# RPi-CM-Adapter.net
KiCad netlist of a schematic drawn in Altium Designer
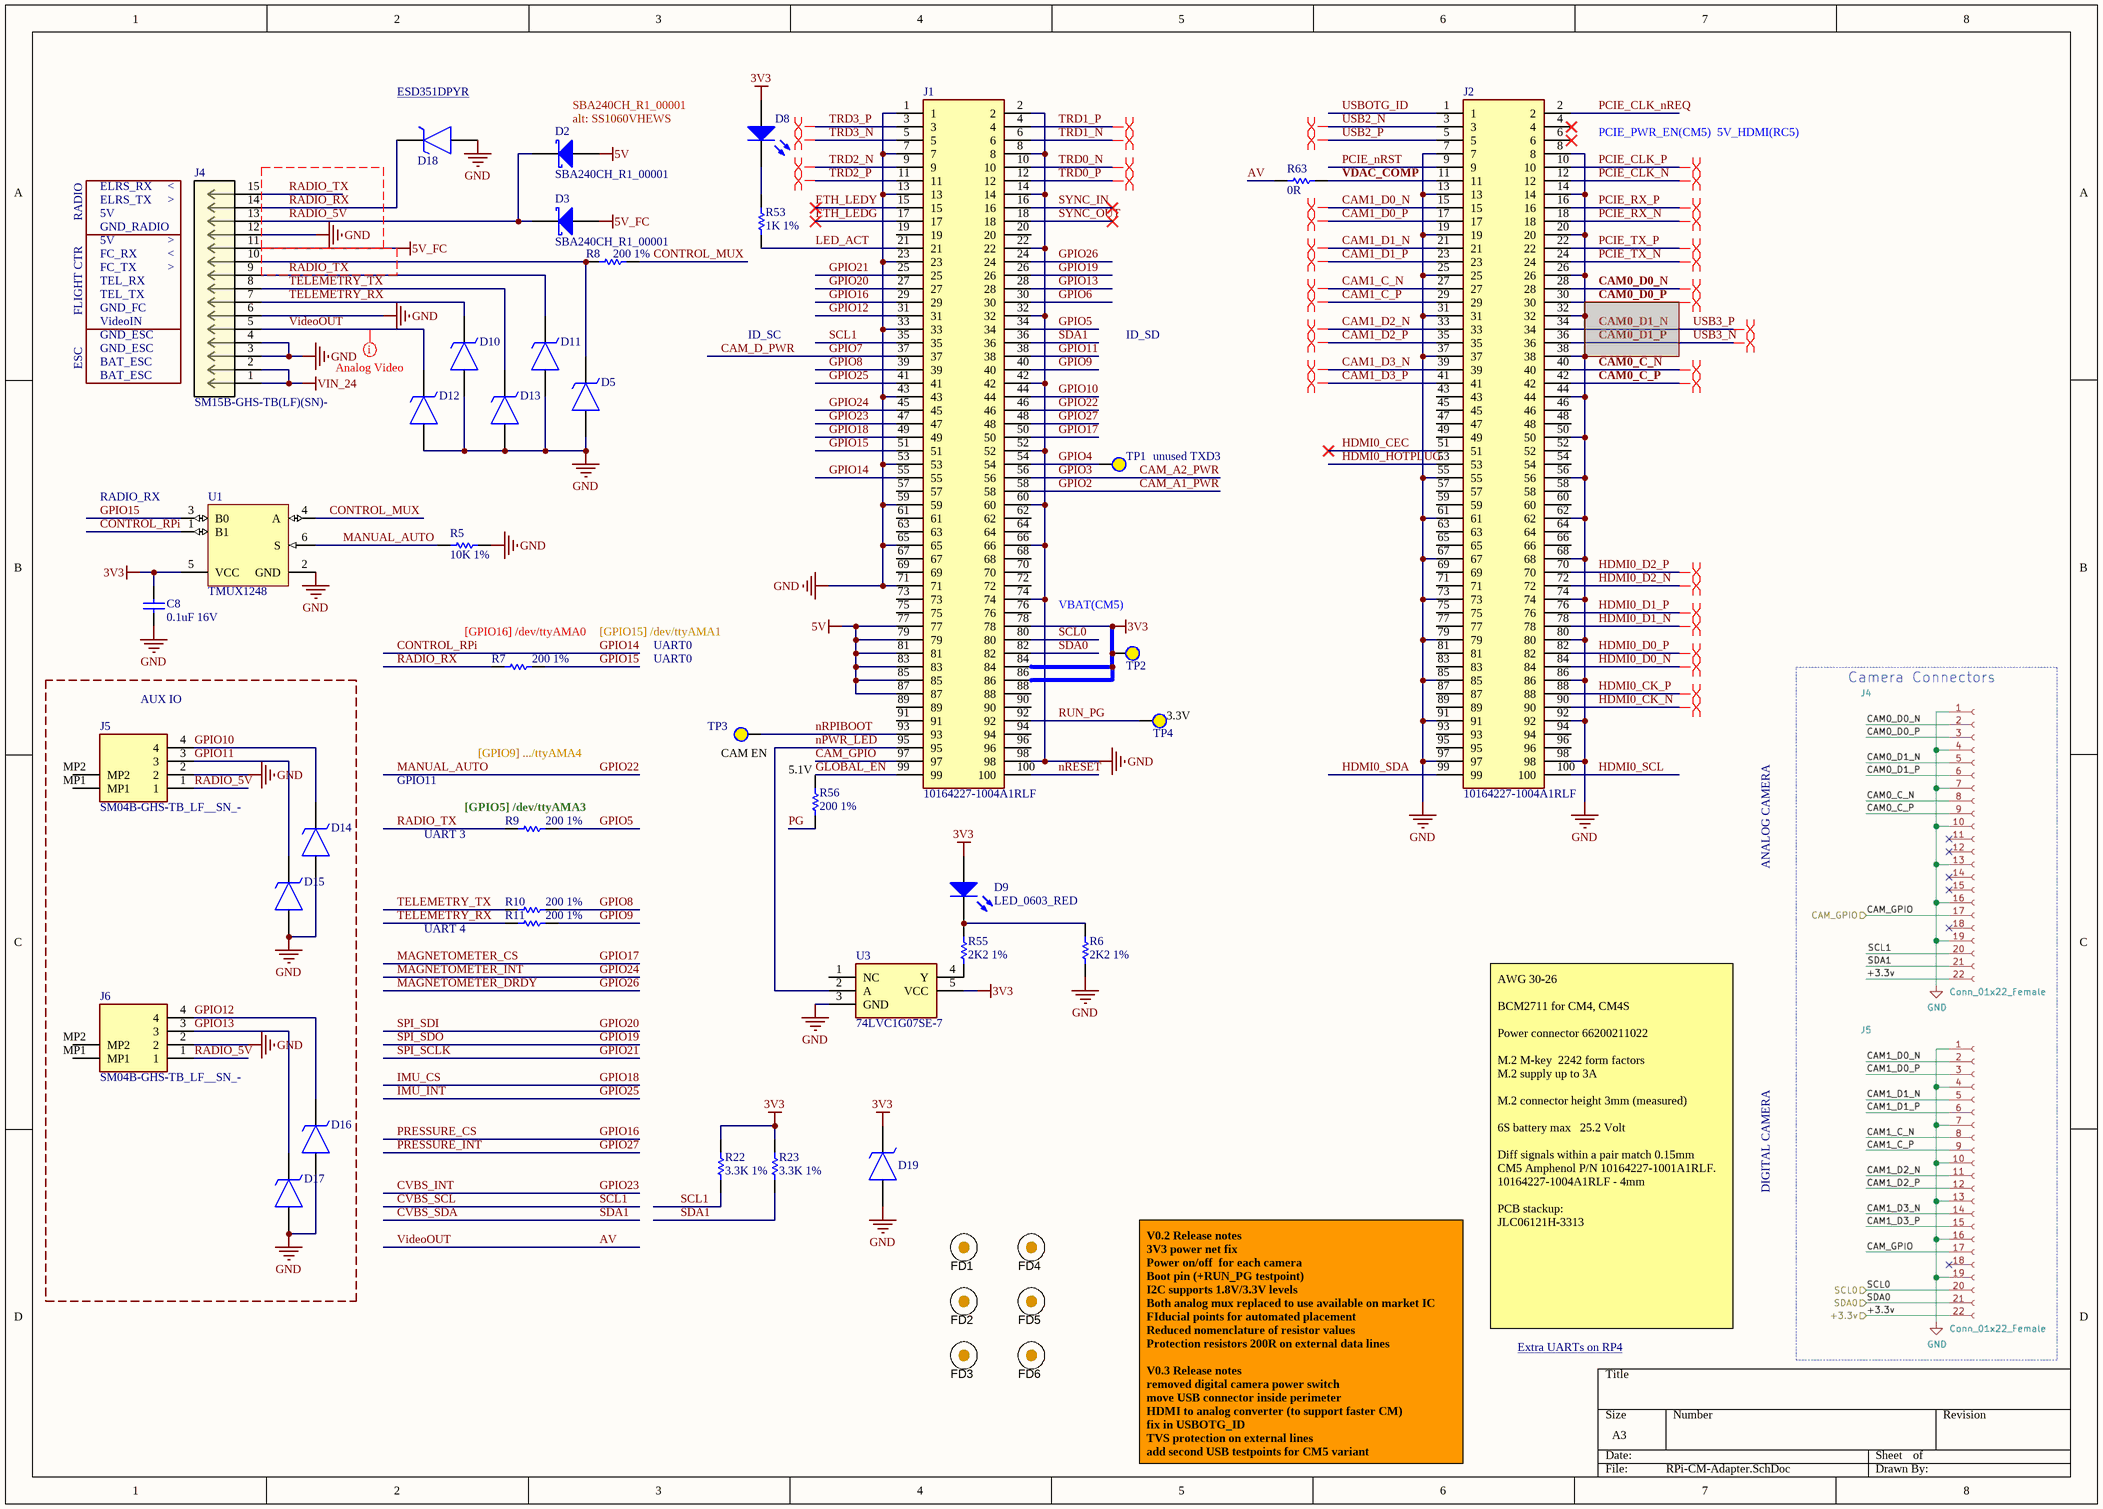
[diagram p0: RPi-CM-Adapter.SchDoc]

(export (version "E")
  (design (tool "Eeschema 10.0.6"))
  (components
    (comp (ref "C8")
      (value "0.1uF 16V")
      (footprint "0402")
      (description "0402 0.1 uF 16V ±10% Tolerance X7R SMT Multilayer Ceramic Capacitor")
      (fields
        (field (name "MANUFACTURER") "Murata")
        (field (name "MANUFACTURER PART NUMBER") "GCM155R71C104KA55J")
      )
      (libsource (lib "MyCustomLibrary") (part "Cap0.1UF_16V_X7R"))
    )
    (comp (ref "D2")
      (value "SBA240CH_R1_00001")
      (footprint "SOD-323HE")
      (description "Diode Schottky 40V 2A SOD323HE")
      (fields (field (name "MANUFACTURER") "Pan Jit"))
      (libsource (lib "MyCustomLibrary") (part "Diode SBA240CH_R1_00001"))
    )
    (comp (ref "D3")
      (value "SBA240CH_R1_00001")
      (footprint "SOD-323HE")
      (description "Diode Schottky 40V 2A SOD323HE")
      (fields (field (name "MANUFACTURER") "Pan Jit"))
      (libsource (lib "MyCustomLibrary") (part "Diode SBA240CH_R1_00001"))
    )
    (comp (ref "D5")
      (value "ESD351DPYR")
      (footprint "UCLAMP2501TTCT")
      (fields (field (name "MANUFACTURER") "Texas Instruments"))
      (libsource (lib "MyCustomLibrary") (part "ESD351DPYR"))
    )
    (comp (ref "D8")
      (value "LED_0603_GREEN")
      (footprint "1608[0603]_DIODE")
      (description "Typical GREEN LED")
      (fields
        (field (name "MANUFACTURER") "Rohm Semiconductor")
        (field (name "MANUFACTURER PART NUMBER") "SML-310MTT86")
      )
      (libsource (lib "MyCustomLibrary") (part "LED_0603_GREEN"))
    )
    (comp (ref "D9")
      (value "LED_0603_RED")
      (footprint "1608[0603]_DIODE")
      (description "Typical RED LED")
      (fields
        (field (name "MANUFACTURER") "Lite-On Inc.")
        (field (name "MANUFACTURER PART NUMBER") "LTST-C193KRKT-5A")
      )
      (libsource (lib "MyCustomLibrary") (part "LED_0603_RED"))
    )
    (comp (ref "D10")
      (value "ESD351DPYR")
      (footprint "UCLAMP2501TTCT")
      (fields (field (name "MANUFACTURER") "Texas Instruments"))
      (libsource (lib "MyCustomLibrary") (part "ESD351DPYR"))
    )
    (comp (ref "D11")
      (value "ESD351DPYR")
      (footprint "UCLAMP2501TTCT")
      (fields (field (name "MANUFACTURER") "Texas Instruments"))
      (libsource (lib "MyCustomLibrary") (part "ESD351DPYR"))
    )
    (comp (ref "D12")
      (value "ESD351DPYR")
      (footprint "UCLAMP2501TTCT")
      (fields (field (name "MANUFACTURER") "Texas Instruments"))
      (libsource (lib "MyCustomLibrary") (part "ESD351DPYR"))
    )
    (comp (ref "D13")
      (value "ESD351DPYR")
      (footprint "UCLAMP2501TTCT")
      (fields (field (name "MANUFACTURER") "Texas Instruments"))
      (libsource (lib "MyCustomLibrary") (part "ESD351DPYR"))
    )
    (comp (ref "D14")
      (value "ESD351DPYR")
      (footprint "UCLAMP2501TTCT")
      (fields (field (name "MANUFACTURER") "Texas Instruments"))
      (libsource (lib "MyCustomLibrary") (part "ESD351DPYR"))
    )
    (comp (ref "D15")
      (value "ESD351DPYR")
      (footprint "UCLAMP2501TTCT")
      (fields (field (name "MANUFACTURER") "Texas Instruments"))
      (libsource (lib "MyCustomLibrary") (part "ESD351DPYR"))
    )
    (comp (ref "D16")
      (value "ESD351DPYR")
      (footprint "UCLAMP2501TTCT")
      (fields (field (name "MANUFACTURER") "Texas Instruments"))
      (libsource (lib "MyCustomLibrary") (part "ESD351DPYR"))
    )
    (comp (ref "D17")
      (value "ESD351DPYR")
      (footprint "UCLAMP2501TTCT")
      (fields (field (name "MANUFACTURER") "Texas Instruments"))
      (libsource (lib "MyCustomLibrary") (part "ESD351DPYR"))
    )
    (comp (ref "D18")
      (value "ESD351DPYR")
      (footprint "UCLAMP2501TTCT")
      (fields (field (name "MANUFACTURER") "Texas Instruments"))
      (libsource (lib "MyCustomLibrary") (part "ESD351DPYR"))
    )
    (comp (ref "D19")
      (value "ESD351DPYR")
      (footprint "UCLAMP2501TTCT")
      (fields (field (name "MANUFACTURER") "Texas Instruments"))
      (libsource (lib "MyCustomLibrary") (part "ESD351DPYR"))
    )
    (comp (ref "FD1")
      (value "Fiducial")
      (footprint "Fiducial10-20")
      (description "Fiducial mark.  There is nothing to buy or mount.")
      (fields (field (name "SYMBOLCREATOR") "codlsc") (field (name "PUBLISHER") "National Semiconductor"))
      (libsource (lib "MyCustomLibrary") (part "Fiducial"))
    )
    (comp (ref "FD2")
      (value "Fiducial")
      (footprint "Fiducial10-20")
      (description "Fiducial mark.  There is nothing to buy or mount.")
      (fields (field (name "SYMBOLCREATOR") "codlsc") (field (name "PUBLISHER") "National Semiconductor"))
      (libsource (lib "MyCustomLibrary") (part "Fiducial"))
    )
    (comp (ref "FD3")
      (value "Fiducial")
      (footprint "Fiducial10-20")
      (description "Fiducial mark.  There is nothing to buy or mount.")
      (fields (field (name "SYMBOLCREATOR") "codlsc") (field (name "PUBLISHER") "National Semiconductor"))
      (libsource (lib "MyCustomLibrary") (part "Fiducial"))
    )
    (comp (ref "FD4")
      (value "Fiducial")
      (footprint "Fiducial10-20")
      (description "Fiducial mark.  There is nothing to buy or mount.")
      (fields (field (name "SYMBOLCREATOR") "codlsc") (field (name "PUBLISHER") "National Semiconductor"))
      (libsource (lib "MyCustomLibrary") (part "Fiducial"))
    )
    (comp (ref "FD5")
      (value "Fiducial")
      (footprint "Fiducial10-20")
      (description "Fiducial mark.  There is nothing to buy or mount.")
      (fields (field (name "SYMBOLCREATOR") "codlsc") (field (name "PUBLISHER") "National Semiconductor"))
      (libsource (lib "MyCustomLibrary") (part "Fiducial"))
    )
    (comp (ref "FD6")
      (value "Fiducial")
      (footprint "Fiducial10-20")
      (description "Fiducial mark.  There is nothing to buy or mount.")
      (fields (field (name "SYMBOLCREATOR") "codlsc") (field (name "PUBLISHER") "National Semiconductor"))
      (libsource (lib "MyCustomLibrary") (part "Fiducial"))
    )
    (comp (ref "J1")
      (value "10164227-1004A1RLF")
      (footprint "MyConnectors:101642271004A1RLF")
      (description "Connector")
      (fields (field (name "MOUSER PART NUMBER") "649-101642271004RLF"))
      (libsource (lib "MyConnectors") (part "10164227-1004A1RLF"))
    )
    (comp (ref "J2")
      (value "10164227-1004A1RLF")
      (footprint "MyConnectors:101642271004A1RLF")
      (description "Connector")
      (fields (field (name "MOUSER PART NUMBER") "649-101642271004RLF"))
      (libsource (lib "MyConnectors") (part "10164227-1004A1RLF"))
    )
    (comp (ref "J4")
      (value "SM15B-GHS-TB(LF)(SN)-")
      (footprint "MyConnectors:CONN_SM15B-GHS-TB")
      (description "No Description Available")
      (libsource (lib "MyConnectors") (part "SM15B-GHS-TB(LF)(SN)-"))
    )
    (comp (ref "J5")
      (value "SM04B-GHS-TB_LF__SN_-")
      (footprint "MyConnectors:SM04BGHSTBLFSN")
      (description "Conn Shrouded Header (4 Sides) HDR 4 POS 1.25mm Solder RA Side Entry SMD T/R")
      (fields
        (field (name "MANUFACTURER_PART_NUMBER") "SM04B-GHS-TB(LF)(SN)-")
        (field (name "MANUFACTURER") "JST")
      )
      (libsource (lib "MyConnectors") (part "SM04B-GHS-TB_LF__SN_-"))
    )
    (comp (ref "J6")
      (value "SM04B-GHS-TB_LF__SN_-")
      (footprint "MyConnectors:SM04BGHSTBLFSN")
      (description "Conn Shrouded Header (4 Sides) HDR 4 POS 1.25mm Solder RA Side Entry SMD T/R")
      (fields
        (field (name "MANUFACTURER_PART_NUMBER") "SM04B-GHS-TB(LF)(SN)-")
        (field (name "MANUFACTURER") "JST")
      )
      (libsource (lib "MyConnectors") (part "SM04B-GHS-TB_LF__SN_-"))
    )
    (comp (ref "R5")
      (value "10K 1%")
      (footprint "0402")
      (description "Resistor")
      (fields
        (field (name "MANUFACTURER") "Yageo")
        (field (name "MANUFACTURER PART NUMBER") "RC0402FR-0710KL")
      )
      (libsource (lib "MyCustomLibrary") (part "Res_10K_0402"))
    )
    (comp (ref "R6")
      (value "2K2 1%")
      (footprint "0402")
      (description "SMD Chip Resistor, 2.2 kOhm, ± 1%, 63 mW, 0402 [1005 Metric], Thick Film, Anti-Sulfur")
      (fields
        (field (name "MANUFACTURER") "Yageo")
        (field (name "MANUFACTURER PART NUMBER") "AF0402FR-072K2L")
      )
      (libsource (lib "MyCustomLibrary") (part "Res_2K2_0402"))
    )
    (comp (ref "R7")
      (value "200 1%")
      (footprint "0402")
      (description "Resistor")
      (libsource (lib "MyCustomLibrary") (part "Res_200R_0402"))
    )
    (comp (ref "R8")
      (value "200 1%")
      (footprint "0402")
      (description "Resistor")
      (libsource (lib "MyCustomLibrary") (part "Res_200R_0402"))
    )
    (comp (ref "R9")
      (value "200 1%")
      (footprint "0402")
      (description "Resistor")
      (libsource (lib "MyCustomLibrary") (part "Res_200R_0402"))
    )
    (comp (ref "R10")
      (value "200 1%")
      (footprint "0402")
      (description "Resistor")
      (libsource (lib "MyCustomLibrary") (part "Res_200R_0402"))
    )
    (comp (ref "R11")
      (value "200 1%")
      (footprint "0402")
      (description "Resistor")
      (libsource (lib "MyCustomLibrary") (part "Res_200R_0402"))
    )
    (comp (ref "R22")
      (value "3.3K 1%")
      (footprint "0402")
      (description "SMD Chip Resistor, Thick Film, 3.3 kohm, 50 V, 0402 [1005 Metric], 1%")
      (fields
        (field (name "MANUFACTURER") "Yageo")
        (field (name "MANUFACTURER PART NUMBER") "RC0402FR-073K3L")
      )
      (libsource (lib "MyCustomLibrary") (part "Res_3K3_0402"))
    )
    (comp (ref "R23")
      (value "3.3K 1%")
      (footprint "0402")
      (description "SMD Chip Resistor, Thick Film, 3.3 kohm, 50 V, 0402 [1005 Metric], 1%")
      (fields
        (field (name "MANUFACTURER") "Yageo")
        (field (name "MANUFACTURER PART NUMBER") "RC0402FR-073K3L")
      )
      (libsource (lib "MyCustomLibrary") (part "Res_3K3_0402"))
    )
    (comp (ref "R53")
      (value "1K 1%")
      (footprint "0402")
      (description "Resistor 1K 1% 0402")
      (fields
        (field (name "MANUFACTURER") "Yageo")
        (field (name "MANUFACTURER PART NUMBER") "RC0402FR-071KL")
      )
      (libsource (lib "MyCustomLibrary") (part "Res_1K_0402"))
    )
    (comp (ref "R55")
      (value "2K2 1%")
      (footprint "0402")
      (description "SMD Chip Resistor, 2.2 kOhm, ± 1%, 63 mW, 0402 [1005 Metric], Thick Film, Anti-Sulfur")
      (fields
        (field (name "MANUFACTURER") "Yageo")
        (field (name "MANUFACTURER PART NUMBER") "AF0402FR-072K2L")
      )
      (libsource (lib "MyCustomLibrary") (part "Res_2K2_0402"))
    )
    (comp (ref "R56")
      (value "200 1%")
      (footprint "0402")
      (description "Resistor")
      (libsource (lib "MyCustomLibrary") (part "Res_200R_0402"))
    )
    (comp (ref "R63")
      (value "0R")
      (footprint "0402")
      (description "Zero ohm Jumper 0402")
      (fields (field (name "TOLERANCE") "Jumper") (field (name "MANUFACTURER") "Yageo"))
      (libsource (lib "MyCustomLibrary") (part "Res_0R_0402"))
    )
    (comp (ref "TP1")
      (value "TESTPOINT")
      (footprint "TESTPOINT_0.9")
      (libsource (lib "MyCustomLibrary") (part "TESTPOINT"))
    )
    (comp (ref "TP2")
      (value "TESTPOINT")
      (footprint "TESTPOINT_0.9")
      (libsource (lib "MyCustomLibrary") (part "TESTPOINT"))
    )
    (comp (ref "TP3")
      (value "TESTPOINT")
      (footprint "TESTPOINT_0.9")
      (libsource (lib "MyCustomLibrary") (part "TESTPOINT"))
    )
    (comp (ref "TP4")
      (value "TESTPOINT")
      (footprint "TESTPOINT_0.9")
      (libsource (lib "MyCustomLibrary") (part "TESTPOINT"))
    )
    (comp (ref "U1")
      (value "TMUX1248")
      (footprint "FAIR-SC70-6_V")
      (description "3-Ω low RON, 5-V, 2: 1 (SPDT) general purpose switch with 3157 pinout 6-SC70 -40 to 125")
      (fields
        (field (name "MANUFACTURER") "Texas Instruments")
        (field (name "MANUFACTURER PART NUMBER") "TMUX1248DCKR")
      )
      (libsource (lib "MyCustomLibrary") (part "TMUX1248"))
    )
    (comp (ref "U3")
      (value "74LVC1G07SE-7")
      (footprint "SamacSys:SOT65P210X110-5N")
      (description "74LVC Series 5.5 V Surface Mount Single Buffer with Open Drain Output - SOT-353")
      (fields (field (name "MOUSER PART NUMBER") "621-74LVC1G07SE-7") (field (name "MANUFACTURER") "Diodes"))
      (libsource (lib "MyCustomLibrary") (part "74LVC1G07SE-7"))
    )
  )
  (nets
    (net (code "1") (name "/AV") (class "Default")
      (node (ref "D12") (pin "2") (pinfunction "K_2") (pintype "passive"))
      (node (ref "J4") (pin "5") (pinfunction "5_5") (pintype "passive"))
      (node (ref "R63") (pin "1") (pinfunction "1_1") (pintype "passive"))
    )
    (net (code "2") (name "/CAM0_C_N") (class "Default")
      (node (ref "J2") (pin "40") (pinfunction "40_40") (pintype "passive"))
    )
    (net (code "3") (name "/CAM0_C_P") (class "Default")
      (node (ref "J2") (pin "42") (pinfunction "42_42") (pintype "passive"))
    )
    (net (code "4") (name "/CAM0_D0_N") (class "Default")
      (node (ref "J2") (pin "28") (pinfunction "28_28") (pintype "passive"))
    )
    (net (code "5") (name "/CAM0_D0_P") (class "Default")
      (node (ref "J2") (pin "30") (pinfunction "30_30") (pintype "passive"))
    )
    (net (code "6") (name "/CAM0_D1_N") (class "Default")
      (node (ref "J2") (pin "34") (pinfunction "34_34") (pintype "passive"))
    )
    (net (code "7") (name "/CAM0_D1_P") (class "Default")
      (node (ref "J2") (pin "36") (pinfunction "36_36") (pintype "passive"))
    )
    (net (code "8") (name "/CAM1_C_N") (class "Default")
      (node (ref "J2") (pin "27") (pinfunction "27_27") (pintype "passive"))
    )
    (net (code "9") (name "/CAM1_C_P") (class "Default")
      (node (ref "J2") (pin "29") (pinfunction "29_29") (pintype "passive"))
    )
    (net (code "10") (name "/CAM1_D0_N") (class "Default")
      (node (ref "J2") (pin "15") (pinfunction "15_15") (pintype "passive"))
    )
    (net (code "11") (name "/CAM1_D0_P") (class "Default")
      (node (ref "J2") (pin "17") (pinfunction "17_17") (pintype "passive"))
    )
    (net (code "12") (name "/CAM1_D1_N") (class "Default")
      (node (ref "J2") (pin "21") (pinfunction "21_21") (pintype "passive"))
    )
    (net (code "13") (name "/CAM1_D1_P") (class "Default")
      (node (ref "J2") (pin "23") (pinfunction "23_23") (pintype "passive"))
    )
    (net (code "14") (name "/CAM1_D2_N") (class "Default")
      (node (ref "J2") (pin "33") (pinfunction "33_33") (pintype "passive"))
    )
    (net (code "15") (name "/CAM1_D2_P") (class "Default")
      (node (ref "J2") (pin "35") (pinfunction "35_35") (pintype "passive"))
    )
    (net (code "16") (name "/CAM1_D3_N") (class "Default")
      (node (ref "J2") (pin "39") (pinfunction "39_39") (pintype "passive"))
    )
    (net (code "17") (name "/CAM1_D3_P") (class "Default")
      (node (ref "J2") (pin "41") (pinfunction "41_41") (pintype "passive"))
    )
    (net (code "18") (name "/CAM_A1_PWR") (class "Default")
      (node (ref "J1") (pin "58") (pinfunction "58_58") (pintype "passive"))
    )
    (net (code "19") (name "/CAM_A2_PWR") (class "Default")
      (node (ref "J1") (pin "56") (pinfunction "56_56") (pintype "passive"))
    )
    (net (code "20") (name "/CAM_D_PWR") (class "Default")
      (node (ref "J1") (pin "37") (pinfunction "37_37") (pintype "passive"))
    )
    (net (code "21") (name "/CAM_GPIO") (class "Default")
      (node (ref "J1") (pin "97") (pinfunction "97_97") (pintype "passive"))
    )
    (net (code "22") (name "/CONTROL_MUX") (class "Default")
      (node (ref "R8") (pin "2") (pinfunction "2_2") (pintype "passive"))
      (node (ref "U1") (pin "4") (pinfunction "A_4") (pintype "bidirectional"))
    )
    (net (code "23") (name "/CONTROL_RPi") (class "Default")
      (node (ref "J1") (pin "55") (pinfunction "55_55") (pintype "passive"))
      (node (ref "U1") (pin "1") (pinfunction "B1_1") (pintype "bidirectional"))
    )
    (net (code "24") (name "/CVBS_INT") (class "Default")
      (node (ref "J1") (pin "47") (pinfunction "47_47") (pintype "passive"))
    )
    (net (code "25") (name "/CVBS_SCL") (class "Default")
      (node (ref "J1") (pin "35") (pinfunction "35_35") (pintype "passive"))
      (node (ref "R22") (pin "1") (pinfunction "1_1") (pintype "passive"))
    )
    (net (code "26") (name "/CVBS_SDA") (class "Default")
      (node (ref "J1") (pin "36") (pinfunction "36_36") (pintype "passive"))
      (node (ref "R23") (pin "1") (pinfunction "1_1") (pintype "passive"))
    )
    (net (code "27") (name "/ETH_LEDG") (class "Default")
      (node (ref "J1") (pin "17") (pinfunction "17_17") (pintype "passive+no_connect"))
    )
    (net (code "28") (name "/ETH_LEDY") (class "Default")
      (node (ref "J1") (pin "15") (pinfunction "15_15") (pintype "passive+no_connect"))
    )
    (net (code "29") (name "/GLOBAL_EN") (class "Default")
      (node (ref "J1") (pin "99") (pinfunction "99_99") (pintype "passive"))
      (node (ref "R56") (pin "2") (pinfunction "2_2") (pintype "passive"))
    )
    (net (code "30") (name "/GPIO4") (class "Default")
      (node (ref "J1") (pin "54") (pinfunction "54_54") (pintype "passive"))
      (node (ref "TP1") (pin "1") (pinfunction "1_1") (pintype "passive"))
    )
    (net (code "31") (name "/GPIO5") (class "Default")
      (node (ref "J1") (pin "34") (pinfunction "34_34") (pintype "passive"))
      (node (ref "R9") (pin "2") (pinfunction "2_2") (pintype "passive"))
    )
    (net (code "32") (name "/GPIO6") (class "Default")
      (node (ref "J1") (pin "30") (pinfunction "30_30") (pintype "passive"))
    )
    (net (code "33") (name "/GPIO8") (class "Default")
      (node (ref "J1") (pin "39") (pinfunction "39_39") (pintype "passive"))
      (node (ref "R10") (pin "2") (pinfunction "2_2") (pintype "passive"))
    )
    (net (code "34") (name "/GPIO9") (class "Default")
      (node (ref "J1") (pin "40") (pinfunction "40_40") (pintype "passive"))
      (node (ref "R11") (pin "2") (pinfunction "2_2") (pintype "passive"))
    )
    (net (code "35") (name "/GPIO10") (class "Default")
      (node (ref "D14") (pin "2") (pinfunction "K_2") (pintype "passive"))
      (node (ref "J1") (pin "44") (pinfunction "44_44") (pintype "passive"))
      (node (ref "J5") (pin "4") (pinfunction "4_4") (pintype "passive"))
    )
    (net (code "36") (name "/GPIO11") (class "Default")
      (node (ref "D15") (pin "2") (pinfunction "K_2") (pintype "passive"))
      (node (ref "J1") (pin "38") (pinfunction "38_38") (pintype "passive"))
      (node (ref "J5") (pin "3") (pinfunction "3_3") (pintype "passive"))
    )
    (net (code "37") (name "/GPIO12") (class "Default")
      (node (ref "D16") (pin "2") (pinfunction "K_2") (pintype "passive"))
      (node (ref "J1") (pin "31") (pinfunction "31_31") (pintype "passive"))
      (node (ref "J6") (pin "4") (pinfunction "4_4") (pintype "passive"))
    )
    (net (code "38") (name "/GPIO13") (class "Default")
      (node (ref "D17") (pin "2") (pinfunction "K_2") (pintype "passive"))
      (node (ref "J1") (pin "28") (pinfunction "28_28") (pintype "passive"))
      (node (ref "J6") (pin "3") (pinfunction "3_3") (pintype "passive"))
    )
    (net (code "39") (name "/GPIO15") (class "Default")
      (node (ref "J1") (pin "51") (pinfunction "51_51") (pintype "passive"))
      (node (ref "R7") (pin "1") (pinfunction "1_1") (pintype "passive"))
      (node (ref "U1") (pin "3") (pinfunction "B0_3") (pintype "bidirectional"))
    )
    (net (code "40") (name "/GPIO16") (class "Default")
      (node (ref "J1") (pin "29") (pinfunction "29_29") (pintype "passive"))
    )
    (net (code "41") (name "/GPIO17") (class "Default")
      (node (ref "J1") (pin "50") (pinfunction "50_50") (pintype "passive"))
    )
    (net (code "42") (name "/GPIO18") (class "Default")
      (node (ref "J1") (pin "49") (pinfunction "49_49") (pintype "passive"))
    )
    (net (code "43") (name "/GPIO19") (class "Default")
      (node (ref "J1") (pin "26") (pinfunction "26_26") (pintype "passive"))
    )
    (net (code "44") (name "/GPIO20") (class "Default")
      (node (ref "J1") (pin "27") (pinfunction "27_27") (pintype "passive"))
    )
    (net (code "45") (name "/GPIO21") (class "Default")
      (node (ref "J1") (pin "25") (pinfunction "25_25") (pintype "passive"))
    )
    (net (code "46") (name "/GPIO22") (class "Default")
      (node (ref "J1") (pin "46") (pinfunction "46_46") (pintype "passive"))
      (node (ref "R5") (pin "2") (pinfunction "2_2") (pintype "passive"))
      (node (ref "U1") (pin "6") (pinfunction "S_6") (pintype "input"))
    )
    (net (code "47") (name "/GPIO24") (class "Default")
      (node (ref "J1") (pin "45") (pinfunction "45_45") (pintype "passive"))
    )
    (net (code "48") (name "/GPIO25") (class "Default")
      (node (ref "J1") (pin "41") (pinfunction "41_41") (pintype "passive"))
    )
    (net (code "49") (name "/GPIO26") (class "Default")
      (node (ref "J1") (pin "24") (pinfunction "24_24") (pintype "passive"))
    )
    (net (code "50") (name "/GPIO27") (class "Default")
      (node (ref "J1") (pin "48") (pinfunction "48_48") (pintype "passive"))
    )
    (net (code "51") (name "/HDMI0_CEC") (class "Default")
      (node (ref "J2") (pin "51") (pinfunction "51_51") (pintype "passive+no_connect"))
    )
    (net (code "52") (name "/HDMI0_CK_N") (class "Default")
      (node (ref "J2") (pin "90") (pinfunction "90_90") (pintype "passive"))
    )
    (net (code "53") (name "/HDMI0_CK_P") (class "Default")
      (node (ref "J2") (pin "88") (pinfunction "88_88") (pintype "passive"))
    )
    (net (code "54") (name "/HDMI0_D0_N") (class "Default")
      (node (ref "J2") (pin "84") (pinfunction "84_84") (pintype "passive"))
    )
    (net (code "55") (name "/HDMI0_D0_P") (class "Default")
      (node (ref "J2") (pin "82") (pinfunction "82_82") (pintype "passive"))
    )
    (net (code "56") (name "/HDMI0_D1_N") (class "Default")
      (node (ref "J2") (pin "78") (pinfunction "78_78") (pintype "passive"))
    )
    (net (code "57") (name "/HDMI0_D1_P") (class "Default")
      (node (ref "J2") (pin "76") (pinfunction "76_76") (pintype "passive"))
    )
    (net (code "58") (name "/HDMI0_D2_N") (class "Default")
      (node (ref "J2") (pin "72") (pinfunction "72_72") (pintype "passive"))
    )
    (net (code "59") (name "/HDMI0_D2_P") (class "Default")
      (node (ref "J2") (pin "70") (pinfunction "70_70") (pintype "passive"))
    )
    (net (code "60") (name "/HDMI0_HOTPLUG") (class "Default")
      (node (ref "J2") (pin "53") (pinfunction "53_53") (pintype "passive"))
    )
    (net (code "61") (name "/HDMI0_SCL") (class "Default")
      (node (ref "J2") (pin "100") (pinfunction "100_100") (pintype "passive"))
    )
    (net (code "62") (name "/HDMI0_SDA") (class "Default")
      (node (ref "J2") (pin "99") (pinfunction "99_99") (pintype "passive"))
    )
    (net (code "63") (name "/LED_ACT") (class "Default")
      (node (ref "J1") (pin "21") (pinfunction "21_21") (pintype "passive"))
      (node (ref "R53") (pin "1") (pinfunction "1_1") (pintype "passive"))
    )
    (net (code "64") (name "/PCIE_CLK_N") (class "Default")
      (node (ref "J2") (pin "12") (pinfunction "12_12") (pintype "passive"))
    )
    (net (code "65") (name "/PCIE_CLK_P") (class "Default")
      (node (ref "J2") (pin "10") (pinfunction "10_10") (pintype "passive"))
    )
    (net (code "66") (name "/PCIE_CLK_nREQ") (class "Default")
      (node (ref "J2") (pin "2") (pinfunction "2_2") (pintype "passive"))
    )
    (net (code "67") (name "/PCIE_RX_N") (class "Default")
      (node (ref "J2") (pin "18") (pinfunction "18_18") (pintype "passive"))
    )
    (net (code "68") (name "/PCIE_RX_P") (class "Default")
      (node (ref "J2") (pin "16") (pinfunction "16_16") (pintype "passive"))
    )
    (net (code "69") (name "/PCIE_TX_N") (class "Default")
      (node (ref "J2") (pin "24") (pinfunction "24_24") (pintype "passive"))
    )
    (net (code "70") (name "/PCIE_TX_P") (class "Default")
      (node (ref "J2") (pin "22") (pinfunction "22_22") (pintype "passive"))
    )
    (net (code "71") (name "/PCIE_nRST") (class "Default")
      (node (ref "J2") (pin "9") (pinfunction "9_9") (pintype "passive"))
    )
    (net (code "72") (name "/PG") (class "Default")
      (node (ref "R56") (pin "1") (pinfunction "1_1") (pintype "passive"))
    )
    (net (code "73") (name "/RADIO_5V") (class "Default")
      (node (ref "D2") (pin "1") (pinfunction "K_1") (pintype "passive"))
      (node (ref "D3") (pin "1") (pinfunction "K_1") (pintype "passive"))
      (node (ref "J4") (pin "13") (pinfunction "13_13") (pintype "passive"))
      (node (ref "J5") (pin "1") (pinfunction "1_1") (pintype "passive"))
      (node (ref "J6") (pin "1") (pinfunction "1_1") (pintype "passive"))
    )
    (net (code "74") (name "/RADIO_RX") (class "Default")
      (node (ref "D18") (pin "2") (pinfunction "K_2") (pintype "passive"))
      (node (ref "J4") (pin "14") (pinfunction "14_14") (pintype "passive"))
      (node (ref "R7") (pin "2") (pinfunction "2_2") (pintype "passive"))
    )
    (net (code "75") (name "/RADIO_TX") (class "Default")
      (node (ref "D11") (pin "2") (pinfunction "K_2") (pintype "passive"))
      (node (ref "J4") (pin "15") (pinfunction "15_15") (pintype "passive"))
      (node (ref "J4") (pin "9") (pinfunction "9_9") (pintype "passive"))
      (node (ref "R9") (pin "1") (pinfunction "1_1") (pintype "passive"))
    )
    (net (code "76") (name "/RUN_PG") (class "Default")
      (node (ref "J1") (pin "92") (pinfunction "92_92") (pintype "passive"))
      (node (ref "TP4") (pin "1") (pinfunction "1_1") (pintype "passive"))
    )
    (net (code "77") (name "/SCL0") (class "Default")
      (node (ref "J1") (pin "80") (pinfunction "80_80") (pintype "passive"))
    )
    (net (code "78") (name "/SDA0") (class "Default")
      (node (ref "J1") (pin "82") (pinfunction "82_82") (pintype "passive"))
    )
    (net (code "79") (name "/SYNC_IN") (class "Default")
      (node (ref "J1") (pin "16") (pinfunction "16_16") (pintype "passive+no_connect"))
    )
    (net (code "80") (name "/SYNC_OUT") (class "Default")
      (node (ref "J1") (pin "18") (pinfunction "18_18") (pintype "passive+no_connect"))
    )
    (net (code "81") (name "/TELEMETRY_RX") (class "Default")
      (node (ref "D10") (pin "2") (pinfunction "K_2") (pintype "passive"))
      (node (ref "J4") (pin "7") (pinfunction "7_7") (pintype "passive"))
      (node (ref "R11") (pin "1") (pinfunction "1_1") (pintype "passive"))
    )
    (net (code "82") (name "/TELEMETRY_TX") (class "Default")
      (node (ref "D13") (pin "2") (pinfunction "K_2") (pintype "passive"))
      (node (ref "J4") (pin "8") (pinfunction "8_8") (pintype "passive"))
      (node (ref "R10") (pin "1") (pinfunction "1_1") (pintype "passive"))
    )
    (net (code "83") (name "/TRD0_N") (class "Default")
      (node (ref "J1") (pin "10") (pinfunction "10_10") (pintype "passive"))
    )
    (net (code "84") (name "/TRD0_P") (class "Default")
      (node (ref "J1") (pin "12") (pinfunction "12_12") (pintype "passive"))
    )
    (net (code "85") (name "/TRD1_N") (class "Default")
      (node (ref "J1") (pin "6") (pinfunction "6_6") (pintype "passive"))
    )
    (net (code "86") (name "/TRD1_P") (class "Default")
      (node (ref "J1") (pin "4") (pinfunction "4_4") (pintype "passive"))
    )
    (net (code "87") (name "/TRD2_N") (class "Default")
      (node (ref "J1") (pin "9") (pinfunction "9_9") (pintype "passive"))
    )
    (net (code "88") (name "/TRD2_P") (class "Default")
      (node (ref "J1") (pin "11") (pinfunction "11_11") (pintype "passive"))
    )
    (net (code "89") (name "/TRD3_N") (class "Default")
      (node (ref "J1") (pin "5") (pinfunction "5_5") (pintype "passive"))
    )
    (net (code "90") (name "/TRD3_P") (class "Default")
      (node (ref "J1") (pin "3") (pinfunction "3_3") (pintype "passive"))
    )
    (net (code "91") (name "/USB2_N") (class "Default")
      (node (ref "J2") (pin "3") (pinfunction "3_3") (pintype "passive"))
    )
    (net (code "92") (name "/USB2_P") (class "Default")
      (node (ref "J2") (pin "5") (pinfunction "5_5") (pintype "passive"))
    )
    (net (code "93") (name "/USBOTG_ID") (class "Default")
      (node (ref "J2") (pin "1") (pinfunction "1_1") (pintype "passive"))
    )
    (net (code "94") (name "/VDAC_COMP") (class "Default")
      (node (ref "J2") (pin "11") (pinfunction "11_11") (pintype "passive"))
      (node (ref "R63") (pin "2") (pinfunction "2_2") (pintype "passive"))
    )
    (net (code "95") (name "/nPWR_LED") (class "Default")
      (node (ref "J1") (pin "95") (pinfunction "95_95") (pintype "passive"))
      (node (ref "U3") (pin "2") (pinfunction "A_2") (pintype "passive"))
    )
    (net (code "96") (name "/nRESET") (class "Default")
      (node (ref "J1") (pin "100") (pinfunction "100_100") (pintype "passive"))
    )
    (net (code "97") (name "/nRPIBOOT") (class "Default")
      (node (ref "J1") (pin "93") (pinfunction "93_93") (pintype "passive"))
      (node (ref "TP3") (pin "1") (pinfunction "1_1") (pintype "passive"))
    )
    (net (code "98") (name "3V3") (class "Default")
      (node (ref "C8") (pin "1") (pinfunction "1_1") (pintype "passive"))
      (node (ref "D19") (pin "2") (pinfunction "K_2") (pintype "passive"))
      (node (ref "D8") (pin "1") (pinfunction "A_1") (pintype "passive"))
      (node (ref "D9") (pin "1") (pinfunction "A_1") (pintype "passive"))
      (node (ref "J1") (pin "78") (pinfunction "78_78") (pintype "passive"))
      (node (ref "J1") (pin "84") (pinfunction "84_84") (pintype "passive"))
      (node (ref "J1") (pin "86") (pinfunction "86_86") (pintype "passive"))
      (node (ref "R22") (pin "2") (pinfunction "2_2") (pintype "passive"))
      (node (ref "R23") (pin "2") (pinfunction "2_2") (pintype "passive"))
      (node (ref "TP2") (pin "1") (pinfunction "1_1") (pintype "passive"))
      (node (ref "U1") (pin "5") (pinfunction "VCC_5") (pintype "power_in"))
      (node (ref "U3") (pin "5") (pinfunction "VCC_5") (pintype "passive"))
    )
    (net (code "99") (name "5V") (class "Default")
      (node (ref "D2") (pin "2") (pinfunction "A_2") (pintype "passive"))
      (node (ref "J1") (pin "77") (pinfunction "77_77") (pintype "passive"))
      (node (ref "J1") (pin "79") (pinfunction "79_79") (pintype "passive"))
      (node (ref "J1") (pin "81") (pinfunction "81_81") (pintype "passive"))
      (node (ref "J1") (pin "83") (pinfunction "83_83") (pintype "passive"))
      (node (ref "J1") (pin "85") (pinfunction "85_85") (pintype "passive"))
      (node (ref "J1") (pin "87") (pinfunction "87_87") (pintype "passive"))
    )
    (net (code "100") (name "5V_FC") (class "Default")
      (node (ref "D3") (pin "2") (pinfunction "A_2") (pintype "passive"))
      (node (ref "J4") (pin "11") (pinfunction "11_11") (pintype "passive"))
    )
    (net (code "101") (name "GND") (class "Default")
      (node (ref "C8") (pin "2") (pinfunction "2_2") (pintype "passive"))
      (node (ref "D10") (pin "1") (pinfunction "A_1") (pintype "passive"))
      (node (ref "D11") (pin "1") (pinfunction "A_1") (pintype "passive"))
      (node (ref "D12") (pin "1") (pinfunction "A_1") (pintype "passive"))
      (node (ref "D13") (pin "1") (pinfunction "A_1") (pintype "passive"))
      (node (ref "D14") (pin "1") (pinfunction "A_1") (pintype "passive"))
      (node (ref "D15") (pin "1") (pinfunction "A_1") (pintype "passive"))
      (node (ref "D16") (pin "1") (pinfunction "A_1") (pintype "passive"))
      (node (ref "D17") (pin "1") (pinfunction "A_1") (pintype "passive"))
      (node (ref "D18") (pin "1") (pinfunction "A_1") (pintype "passive"))
      (node (ref "D19") (pin "1") (pinfunction "A_1") (pintype "passive"))
      (node (ref "D5") (pin "1") (pinfunction "A_1") (pintype "passive"))
      (node (ref "J1") (pin "1") (pinfunction "1_1") (pintype "passive"))
      (node (ref "J1") (pin "13") (pinfunction "13_13") (pintype "passive"))
      (node (ref "J1") (pin "14") (pinfunction "14_14") (pintype "passive"))
      (node (ref "J1") (pin "2") (pinfunction "2_2") (pintype "passive"))
      (node (ref "J1") (pin "22") (pinfunction "22_22") (pintype "passive"))
      (node (ref "J1") (pin "23") (pinfunction "23_23") (pintype "passive"))
      (node (ref "J1") (pin "32") (pinfunction "32_32") (pintype "passive"))
      (node (ref "J1") (pin "33") (pinfunction "33_33") (pintype "passive"))
      (node (ref "J1") (pin "42") (pinfunction "42_42") (pintype "passive"))
      (node (ref "J1") (pin "43") (pinfunction "43_43") (pintype "passive"))
      (node (ref "J1") (pin "52") (pinfunction "52_52") (pintype "passive"))
      (node (ref "J1") (pin "53") (pinfunction "53_53") (pintype "passive"))
      (node (ref "J1") (pin "59") (pinfunction "59_59") (pintype "passive"))
      (node (ref "J1") (pin "60") (pinfunction "60_60") (pintype "passive"))
      (node (ref "J1") (pin "65") (pinfunction "65_65") (pintype "passive"))
      (node (ref "J1") (pin "66") (pinfunction "66_66") (pintype "passive"))
      (node (ref "J1") (pin "7") (pinfunction "7_7") (pintype "passive"))
      (node (ref "J1") (pin "71") (pinfunction "71_71") (pintype "passive"))
      (node (ref "J1") (pin "74") (pinfunction "74_74") (pintype "passive"))
      (node (ref "J1") (pin "8") (pinfunction "8_8") (pintype "passive"))
      (node (ref "J1") (pin "98") (pinfunction "98_98") (pintype "passive"))
      (node (ref "J2") (pin "13") (pinfunction "13_13") (pintype "passive"))
      (node (ref "J2") (pin "14") (pinfunction "14_14") (pintype "passive"))
      (node (ref "J2") (pin "19") (pinfunction "19_19") (pintype "passive"))
      (node (ref "J2") (pin "20") (pinfunction "20_20") (pintype "passive"))
      (node (ref "J2") (pin "25") (pinfunction "25_25") (pintype "passive"))
      (node (ref "J2") (pin "26") (pinfunction "26_26") (pintype "passive"))
      (node (ref "J2") (pin "31") (pinfunction "31_31") (pintype "passive"))
      (node (ref "J2") (pin "32") (pinfunction "32_32") (pintype "passive"))
      (node (ref "J2") (pin "37") (pinfunction "37_37") (pintype "passive"))
      (node (ref "J2") (pin "38") (pinfunction "38_38") (pintype "passive"))
      (node (ref "J2") (pin "44") (pinfunction "44_44") (pintype "passive"))
      (node (ref "J2") (pin "50") (pinfunction "50_50") (pintype "passive"))
      (node (ref "J2") (pin "55") (pinfunction "55_55") (pintype "passive"))
      (node (ref "J2") (pin "56") (pinfunction "56_56") (pintype "passive"))
      (node (ref "J2") (pin "61") (pinfunction "61_61") (pintype "passive"))
      (node (ref "J2") (pin "62") (pinfunction "62_62") (pintype "passive"))
      (node (ref "J2") (pin "67") (pinfunction "67_67") (pintype "passive"))
      (node (ref "J2") (pin "68") (pinfunction "68_68") (pintype "passive"))
      (node (ref "J2") (pin "7") (pinfunction "7_7") (pintype "passive"))
      (node (ref "J2") (pin "73") (pinfunction "73_73") (pintype "passive"))
      (node (ref "J2") (pin "74") (pinfunction "74_74") (pintype "passive"))
      (node (ref "J2") (pin "79") (pinfunction "79_79") (pintype "passive"))
      (node (ref "J2") (pin "8") (pinfunction "8_8") (pintype "passive"))
      (node (ref "J2") (pin "80") (pinfunction "80_80") (pintype "passive"))
      (node (ref "J2") (pin "85") (pinfunction "85_85") (pintype "passive"))
      (node (ref "J2") (pin "86") (pinfunction "86_86") (pintype "passive"))
      (node (ref "J2") (pin "91") (pinfunction "91_91") (pintype "passive"))
      (node (ref "J2") (pin "92") (pinfunction "92_92") (pintype "passive"))
      (node (ref "J2") (pin "97") (pinfunction "97_97") (pintype "passive"))
      (node (ref "J2") (pin "98") (pinfunction "98_98") (pintype "passive"))
      (node (ref "J4") (pin "12") (pinfunction "12_12") (pintype "passive"))
      (node (ref "J4") (pin "3") (pinfunction "3_3") (pintype "passive"))
      (node (ref "J4") (pin "4") (pinfunction "4_4") (pintype "passive"))
      (node (ref "J4") (pin "6") (pinfunction "6_6") (pintype "passive"))
      (node (ref "J5") (pin "2") (pinfunction "2_2") (pintype "passive"))
      (node (ref "J6") (pin "2") (pinfunction "2_2") (pintype "passive"))
      (node (ref "R5") (pin "1") (pinfunction "1_1") (pintype "passive"))
      (node (ref "R6") (pin "1") (pinfunction "1_1") (pintype "passive"))
      (node (ref "U1") (pin "2") (pinfunction "GND_2") (pintype "power_in"))
      (node (ref "U3") (pin "3") (pinfunction "GND_3") (pintype "passive"))
    )
    (net (code "102") (name "Net-(D5-K)") (class "Default")
      (node (ref "D5") (pin "2") (pinfunction "K_2") (pintype "passive"))
      (node (ref "J4") (pin "10") (pinfunction "10_10") (pintype "passive"))
      (node (ref "R8") (pin "1") (pinfunction "1_1") (pintype "passive"))
    )
    (net (code "103") (name "Net-(D8-K)") (class "Default")
      (node (ref "D8") (pin "2") (pinfunction "K_2") (pintype "passive"))
      (node (ref "R53") (pin "2") (pinfunction "2_2") (pintype "passive"))
    )
    (net (code "104") (name "Net-(D9-K)") (class "Default")
      (node (ref "D9") (pin "2") (pinfunction "K_2") (pintype "passive"))
      (node (ref "R55") (pin "2") (pinfunction "2_2") (pintype "passive"))
      (node (ref "R6") (pin "2") (pinfunction "2_2") (pintype "passive"))
    )
    (net (code "105") (name "Net-(U3-Y)") (class "Default")
      (node (ref "R55") (pin "1") (pinfunction "1_1") (pintype "passive"))
      (node (ref "U3") (pin "4") (pinfunction "Y_4") (pintype "passive"))
    )
    (net (code "106") (name "VIN_24") (class "Default")
      (node (ref "J4") (pin "1") (pinfunction "1_1") (pintype "passive"))
      (node (ref "J4") (pin "2") (pinfunction "2_2") (pintype "passive"))
    )
    (net (code "107") (name "unconnected-(J1-Pad19)") (class "Default")
      (node (ref "J1") (pin "19") (pinfunction "19_19") (pintype "passive"))
    )
    (net (code "108") (name "unconnected-(J1-Pad20)") (class "Default")
      (node (ref "J1") (pin "20") (pinfunction "20_20") (pintype "passive"))
    )
    (net (code "109") (name "unconnected-(J1-Pad57)") (class "Default")
      (node (ref "J1") (pin "57") (pinfunction "57_57") (pintype "passive"))
    )
    (net (code "110") (name "unconnected-(J1-Pad61)") (class "Default")
      (node (ref "J1") (pin "61") (pinfunction "61_61") (pintype "passive"))
    )
    (net (code "111") (name "unconnected-(J1-Pad62)") (class "Default")
      (node (ref "J1") (pin "62") (pinfunction "62_62") (pintype "passive"))
    )
    (net (code "112") (name "unconnected-(J1-Pad63)") (class "Default")
      (node (ref "J1") (pin "63") (pinfunction "63_63") (pintype "passive"))
    )
    (net (code "113") (name "unconnected-(J1-Pad64)") (class "Default")
      (node (ref "J1") (pin "64") (pinfunction "64_64") (pintype "passive"))
    )
    (net (code "114") (name "unconnected-(J1-Pad67)") (class "Default")
      (node (ref "J1") (pin "67") (pinfunction "67_67") (pintype "passive"))
    )
    (net (code "115") (name "unconnected-(J1-Pad68)") (class "Default")
      (node (ref "J1") (pin "68") (pinfunction "68_68") (pintype "passive"))
    )
    (net (code "116") (name "unconnected-(J1-Pad69)") (class "Default")
      (node (ref "J1") (pin "69") (pinfunction "69_69") (pintype "passive"))
    )
    (net (code "117") (name "unconnected-(J1-Pad70)") (class "Default")
      (node (ref "J1") (pin "70") (pinfunction "70_70") (pintype "passive"))
    )
    (net (code "118") (name "unconnected-(J1-Pad72)") (class "Default")
      (node (ref "J1") (pin "72") (pinfunction "72_72") (pintype "passive"))
    )
    (net (code "119") (name "unconnected-(J1-Pad73)") (class "Default")
      (node (ref "J1") (pin "73") (pinfunction "73_73") (pintype "passive"))
    )
    (net (code "120") (name "unconnected-(J1-Pad75)") (class "Default")
      (node (ref "J1") (pin "75") (pinfunction "75_75") (pintype "passive"))
    )
    (net (code "121") (name "unconnected-(J1-Pad76)") (class "Default")
      (node (ref "J1") (pin "76") (pinfunction "76_76") (pintype "passive"))
    )
    (net (code "122") (name "unconnected-(J1-Pad88)") (class "Default")
      (node (ref "J1") (pin "88") (pinfunction "88_88") (pintype "passive"))
    )
    (net (code "123") (name "unconnected-(J1-Pad89)") (class "Default")
      (node (ref "J1") (pin "89") (pinfunction "89_89") (pintype "passive"))
    )
    (net (code "124") (name "unconnected-(J1-Pad90)") (class "Default")
      (node (ref "J1") (pin "90") (pinfunction "90_90") (pintype "passive"))
    )
    (net (code "125") (name "unconnected-(J1-Pad91)") (class "Default")
      (node (ref "J1") (pin "91") (pinfunction "91_91") (pintype "passive"))
    )
    (net (code "126") (name "unconnected-(J1-Pad94)") (class "Default")
      (node (ref "J1") (pin "94") (pinfunction "94_94") (pintype "passive"))
    )
    (net (code "127") (name "unconnected-(J1-Pad96)") (class "Default")
      (node (ref "J1") (pin "96") (pinfunction "96_96") (pintype "passive"))
    )
    (net (code "128") (name "unconnected-(J2-Pad4)") (class "Default")
      (node (ref "J2") (pin "4") (pinfunction "4_4") (pintype "passive+no_connect"))
    )
    (net (code "129") (name "unconnected-(J2-Pad6)") (class "Default")
      (node (ref "J2") (pin "6") (pinfunction "6_6") (pintype "passive+no_connect"))
    )
    (net (code "130") (name "unconnected-(J2-Pad43)") (class "Default")
      (node (ref "J2") (pin "43") (pinfunction "43_43") (pintype "passive"))
    )
    (net (code "131") (name "unconnected-(J2-Pad45)") (class "Default")
      (node (ref "J2") (pin "45") (pinfunction "45_45") (pintype "passive"))
    )
    (net (code "132") (name "unconnected-(J2-Pad46)") (class "Default")
      (node (ref "J2") (pin "46") (pinfunction "46_46") (pintype "passive"))
    )
    (net (code "133") (name "unconnected-(J2-Pad47)") (class "Default")
      (node (ref "J2") (pin "47") (pinfunction "47_47") (pintype "passive"))
    )
    (net (code "134") (name "unconnected-(J2-Pad48)") (class "Default")
      (node (ref "J2") (pin "48") (pinfunction "48_48") (pintype "passive"))
    )
    (net (code "135") (name "unconnected-(J2-Pad49)") (class "Default")
      (node (ref "J2") (pin "49") (pinfunction "49_49") (pintype "passive"))
    )
    (net (code "136") (name "unconnected-(J2-Pad52)") (class "Default")
      (node (ref "J2") (pin "52") (pinfunction "52_52") (pintype "passive"))
    )
    (net (code "137") (name "unconnected-(J2-Pad54)") (class "Default")
      (node (ref "J2") (pin "54") (pinfunction "54_54") (pintype "passive"))
    )
    (net (code "138") (name "unconnected-(J2-Pad57)") (class "Default")
      (node (ref "J2") (pin "57") (pinfunction "57_57") (pintype "passive"))
    )
    (net (code "139") (name "unconnected-(J2-Pad58)") (class "Default")
      (node (ref "J2") (pin "58") (pinfunction "58_58") (pintype "passive"))
    )
    (net (code "140") (name "unconnected-(J2-Pad59)") (class "Default")
      (node (ref "J2") (pin "59") (pinfunction "59_59") (pintype "passive"))
    )
    (net (code "141") (name "unconnected-(J2-Pad60)") (class "Default")
      (node (ref "J2") (pin "60") (pinfunction "60_60") (pintype "passive"))
    )
    (net (code "142") (name "unconnected-(J2-Pad63)") (class "Default")
      (node (ref "J2") (pin "63") (pinfunction "63_63") (pintype "passive"))
    )
    (net (code "143") (name "unconnected-(J2-Pad64)") (class "Default")
      (node (ref "J2") (pin "64") (pinfunction "64_64") (pintype "passive"))
    )
    (net (code "144") (name "unconnected-(J2-Pad65)") (class "Default")
      (node (ref "J2") (pin "65") (pinfunction "65_65") (pintype "passive"))
    )
    (net (code "145") (name "unconnected-(J2-Pad66)") (class "Default")
      (node (ref "J2") (pin "66") (pinfunction "66_66") (pintype "passive"))
    )
    (net (code "146") (name "unconnected-(J2-Pad69)") (class "Default")
      (node (ref "J2") (pin "69") (pinfunction "69_69") (pintype "passive"))
    )
    (net (code "147") (name "unconnected-(J2-Pad71)") (class "Default")
      (node (ref "J2") (pin "71") (pinfunction "71_71") (pintype "passive"))
    )
    (net (code "148") (name "unconnected-(J2-Pad75)") (class "Default")
      (node (ref "J2") (pin "75") (pinfunction "75_75") (pintype "passive"))
    )
    (net (code "149") (name "unconnected-(J2-Pad77)") (class "Default")
      (node (ref "J2") (pin "77") (pinfunction "77_77") (pintype "passive"))
    )
    (net (code "150") (name "unconnected-(J2-Pad81)") (class "Default")
      (node (ref "J2") (pin "81") (pinfunction "81_81") (pintype "passive"))
    )
    (net (code "151") (name "unconnected-(J2-Pad83)") (class "Default")
      (node (ref "J2") (pin "83") (pinfunction "83_83") (pintype "passive"))
    )
    (net (code "152") (name "unconnected-(J2-Pad87)") (class "Default")
      (node (ref "J2") (pin "87") (pinfunction "87_87") (pintype "passive"))
    )
    (net (code "153") (name "unconnected-(J2-Pad89)") (class "Default")
      (node (ref "J2") (pin "89") (pinfunction "89_89") (pintype "passive"))
    )
    (net (code "154") (name "unconnected-(J2-Pad93)") (class "Default")
      (node (ref "J2") (pin "93") (pinfunction "93_93") (pintype "passive"))
    )
    (net (code "155") (name "unconnected-(J2-Pad94)") (class "Default")
      (node (ref "J2") (pin "94") (pinfunction "94_94") (pintype "passive"))
    )
    (net (code "156") (name "unconnected-(J2-Pad95)") (class "Default")
      (node (ref "J2") (pin "95") (pinfunction "95_95") (pintype "passive"))
    )
    (net (code "157") (name "unconnected-(J2-Pad96)") (class "Default")
      (node (ref "J2") (pin "96") (pinfunction "96_96") (pintype "passive"))
    )
    (net (code "158") (name "unconnected-(J5-PadMP1)") (class "Default")
      (node (ref "J5") (pin "MP1") (pinfunction "MP1_MP1") (pintype "passive"))
    )
    (net (code "159") (name "unconnected-(J5-PadMP2)") (class "Default")
      (node (ref "J5") (pin "MP2") (pinfunction "MP2_MP2") (pintype "passive"))
    )
    (net (code "160") (name "unconnected-(J6-PadMP1)") (class "Default")
      (node (ref "J6") (pin "MP1") (pinfunction "MP1_MP1") (pintype "passive"))
    )
    (net (code "161") (name "unconnected-(J6-PadMP2)") (class "Default")
      (node (ref "J6") (pin "MP2") (pinfunction "MP2_MP2") (pintype "passive"))
    )
    (net (code "162") (name "unconnected-(U3-NC-Pad1)") (class "Default")
      (node (ref "U3") (pin "1") (pinfunction "NC_1") (pintype "passive"))
    )
  )
)
